# Aux_Lights_Daughter_REV2.net
KiCad netlist of a schematic drawn in Altium Designer
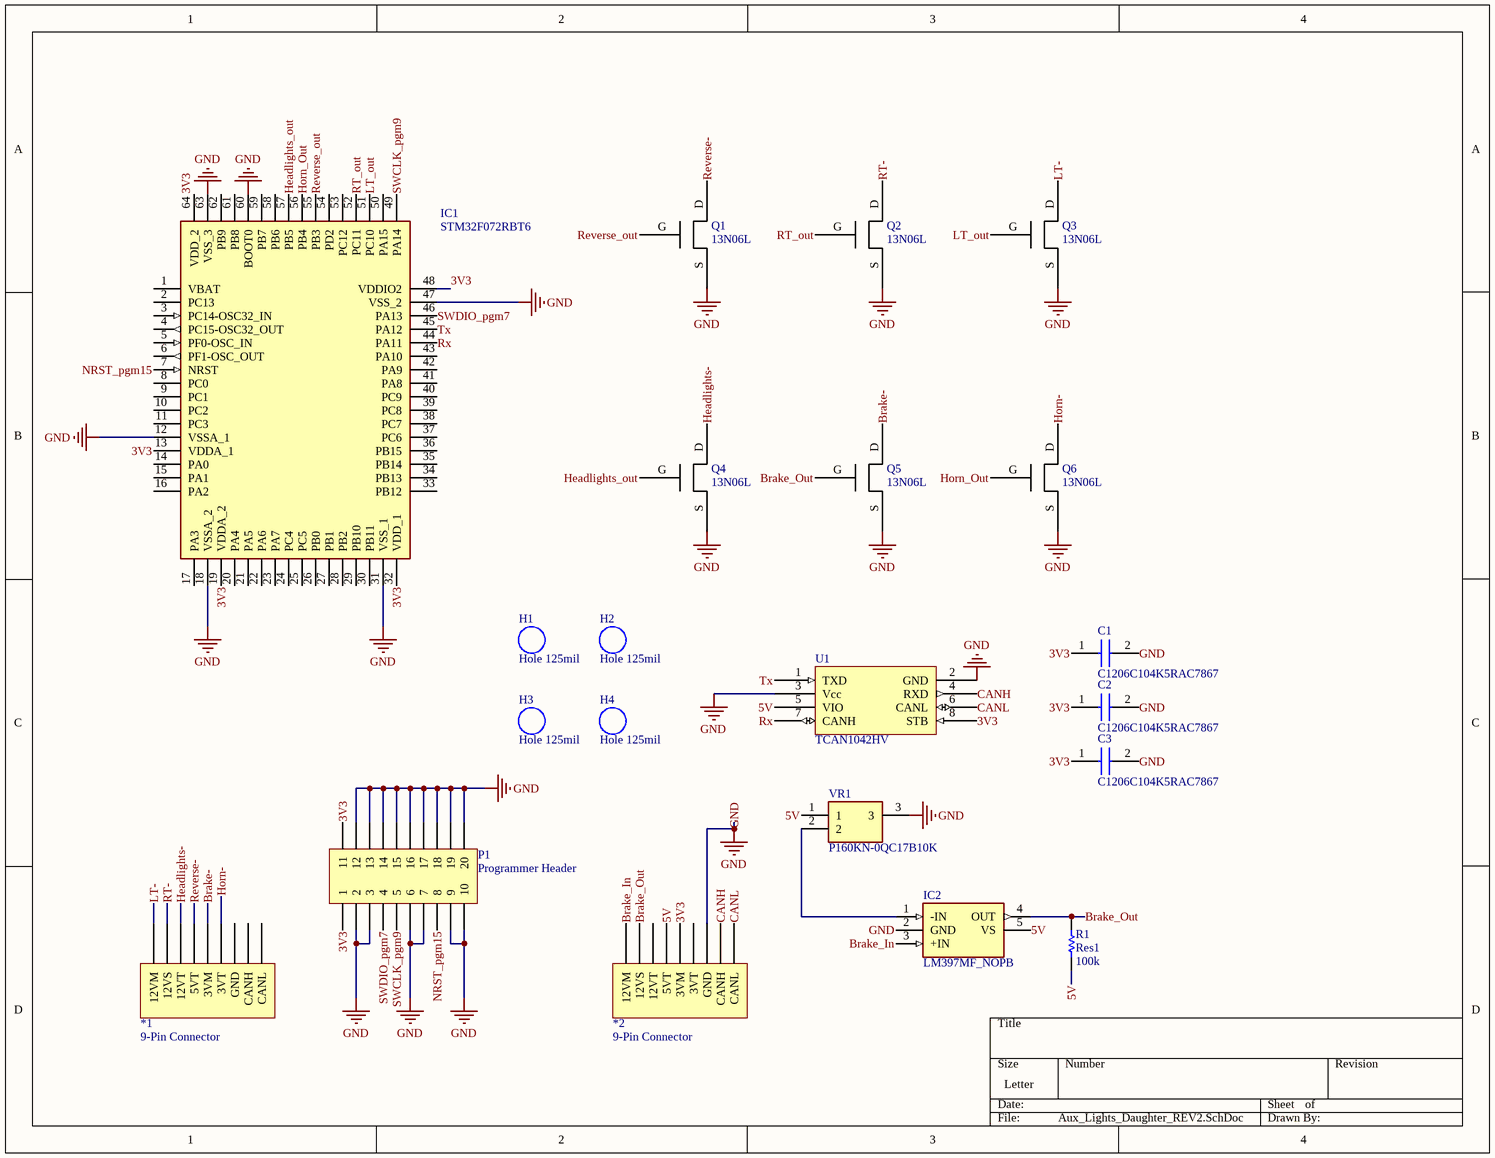
[diagram p0: Aux_Lights_Daughter_REV2.SchDoc]

(export (version "E")
  (design (tool "Eeschema 10.0.6"))
  (components
    (comp (ref "*1")
      (value "9-Pin Connector")
      (footprint "9-Pin")
      (libsource (lib "SolarGators") (part "9-Pin Connector"))
    )
    (comp (ref "*2")
      (value "9-Pin Connector")
      (footprint "9-Pin")
      (libsource (lib "SolarGators") (part "9-Pin Connector"))
    )
    (comp (ref "C1")
      (value "C1206C104K5RAC7867")
      (footprint "SamacSys:CAPC3216X110N")
      (description "Capacitor")
      (fields (field (name "MOUSER2 PART NUMBER") "80-C1206104K5RAC7867"))
      (libsource (lib "*") (part "C1206C104K5RAC7867"))
    )
    (comp (ref "C2")
      (value "C1206C104K5RAC7867")
      (footprint "SamacSys:CAPC3216X110N")
      (description "Capacitor")
      (fields (field (name "MOUSER2 PART NUMBER") "80-C1206104K5RAC7867"))
      (libsource (lib "*") (part "C1206C104K5RAC7867"))
    )
    (comp (ref "C3")
      (value "C1206C104K5RAC7867")
      (footprint "SamacSys:CAPC3216X110N")
      (description "Capacitor")
      (fields (field (name "MOUSER2 PART NUMBER") "80-C1206104K5RAC7867"))
      (libsource (lib "*") (part "C1206C104K5RAC7867"))
    )
    (comp (ref "H1")
      (value "Hole 125mil")
      (footprint "Hole 125mil")
      (libsource (lib "ECE LIB new") (part "Hole 125mil"))
    )
    (comp (ref "H2")
      (value "Hole 125mil")
      (footprint "Hole 125mil")
      (libsource (lib "ECE LIB new") (part "Hole 125mil"))
    )
    (comp (ref "H3")
      (value "Hole 125mil")
      (footprint "Hole 125mil")
      (libsource (lib "ECE LIB new") (part "Hole 125mil"))
    )
    (comp (ref "H4")
      (value "Hole 125mil")
      (footprint "Hole 125mil")
      (libsource (lib "ECE LIB new") (part "Hole 125mil"))
    )
    (comp (ref "IC1")
      (value "STM32F072RBT6")
      (footprint "QFP50P1200X1200X160-64N")
      (description "Integrated Circuit")
      (fields (field (name "MOUSER PART NUMBER") "511-STM32F072RBT6"))
      (libsource (lib "solargatorsproject") (part "STM32F072RBT6"))
    )
    (comp (ref "IC2")
      (value "LM397MF_NOPB")
      (footprint "SamacSys:SOT95P280X145-5N")
      (description "Integrated Circuit")
      (fields
        (field (name "MOUSER PART NUMBER") "926-LM397MF/NOPB")
        (field (name "MANUFACTURER_PART_NUMBER") "LM397MF/NOPB")
      )
      (libsource (lib "*") (part "LM397MF_NOPB"))
    )
    (comp (ref "P1")
      (value "Programmer Header")
      (footprint "HDR2X10_CEN")
      (description "Header, 10-Pin, Dual row")
      (fields (field (name "PUBLISHER") "Altium Limited"))
      (libsource (lib "Miscellaneous Connectors") (part "Header 10X2A"))
    )
    (comp (ref "Q1") (value "13N06L") (footprint "13N06L") (libsource (lib "SolarGators") (part "13N06L")))
    (comp (ref "Q2") (value "13N06L") (footprint "13N06L") (libsource (lib "SolarGators") (part "13N06L")))
    (comp (ref "Q3") (value "13N06L") (footprint "13N06L") (libsource (lib "SolarGators") (part "13N06L")))
    (comp (ref "Q4") (value "13N06L") (footprint "13N06L") (libsource (lib "SolarGators") (part "13N06L")))
    (comp (ref "Q5") (value "13N06L") (footprint "13N06L") (libsource (lib "SolarGators") (part "13N06L")))
    (comp (ref "Q6") (value "13N06L") (footprint "13N06L") (libsource (lib "SolarGators") (part "13N06L")))
    (comp (ref "R1")
      (value "Res1")
      (footprint "AXIAL-0.3")
      (description "Resistor")
      (fields (field (name "ALTIUM_VALUE") "100k") (field (name "PUBLISHER") "Altium Limited"))
      (libsource (lib "Miscellaneous Devices") (part "Res1"))
    )
    (comp (ref "U1")
      (value "TCAN1042HV")
      (footprint "CANIC")
      (description "TCAN1042Fault ProtectedCAN Transceiverwith CAN FD")
      (libsource (lib "Schlib1") (part "TCAN1042HV"))
    )
    (comp (ref "VR1")
      (value "P160KN-0QC17B10K")
      (footprint "POT inline wide")
      (description "Variable Resistor")
      (fields (field (name "MOUSER PART NUMBER") "858-P160KN-OQC17B10K"))
      (libsource (lib "*") (part "P160KN-0QC17B10K"))
    )
  )
  (nets
    (net (code "1") (name "/3V3") (class "Default")
      (node (ref "*2") (pin "5") (pinfunction "3VM_5") (pintype "passive"))
      (node (ref "C1") (pin "1") (pinfunction "1_1") (pintype "passive"))
      (node (ref "C2") (pin "1") (pinfunction "1_1") (pintype "passive"))
      (node (ref "C3") (pin "1") (pinfunction "1_1") (pintype "passive"))
      (node (ref "IC1") (pin "13") (pinfunction "VDDA_1_13") (pintype "power_in"))
      (node (ref "IC1") (pin "19") (pinfunction "VDDA_2_19") (pintype "power_in"))
      (node (ref "IC1") (pin "32") (pinfunction "VDD_1_32") (pintype "power_in"))
      (node (ref "IC1") (pin "48") (pinfunction "VDDIO2_48") (pintype "power_in"))
      (node (ref "IC1") (pin "64") (pinfunction "VDD_2_64") (pintype "power_in"))
      (node (ref "P1") (pin "1") (pinfunction "1_1") (pintype "passive"))
      (node (ref "P1") (pin "11") (pinfunction "11_11") (pintype "passive"))
      (node (ref "U1") (pin "8") (pinfunction "STB_8") (pintype "input"))
    )
    (net (code "2") (name "/5V") (class "Default")
      (node (ref "*2") (pin "4") (pinfunction "5VT_4") (pintype "passive"))
      (node (ref "IC2") (pin "5") (pinfunction "VS_5") (pintype "passive"))
      (node (ref "R1") (pin "1") (pinfunction "1_1") (pintype "passive"))
      (node (ref "U1") (pin "5") (pinfunction "VIO_5") (pintype "power_in"))
      (node (ref "VR1") (pin "1") (pinfunction "1_1") (pintype "passive"))
    )
    (net (code "3") (name "/Brake-") (class "Default")
      (node (ref "*1") (pin "5") (pinfunction "3VM_5") (pintype "passive"))
      (node (ref "Q5") (pin "D") (pinfunction "14_D") (pintype "passive"))
    )
    (net (code "4") (name "/Brake_In") (class "Default")
      (node (ref "*2") (pin "1") (pinfunction "12VM_1") (pintype "passive"))
      (node (ref "IC2") (pin "3") (pinfunction "+IN_3") (pintype "input"))
    )
    (net (code "5") (name "/Brake_Out") (class "Default")
      (node (ref "*2") (pin "2") (pinfunction "12VS_2") (pintype "passive"))
      (node (ref "IC2") (pin "4") (pinfunction "OUT_4") (pintype "output"))
      (node (ref "Q5") (pin "G") (pinfunction "13_G") (pintype "passive"))
      (node (ref "R1") (pin "2") (pinfunction "2_2") (pintype "passive"))
    )
    (net (code "6") (name "/CANH") (class "Default")
      (node (ref "*2") (pin "8") (pinfunction "CANH_8") (pintype "passive"))
      (node (ref "U1") (pin "4") (pinfunction "RXD_4") (pintype "output"))
    )
    (net (code "7") (name "/CANL") (class "Default")
      (node (ref "*2") (pin "9") (pinfunction "CANL_9") (pintype "passive"))
      (node (ref "U1") (pin "6") (pinfunction "CANL_6") (pintype "bidirectional"))
    )
    (net (code "8") (name "/Headlights-") (class "Default")
      (node (ref "*1") (pin "3") (pinfunction "12VT_3") (pintype "passive"))
      (node (ref "Q4") (pin "D") (pinfunction "14_D") (pintype "passive"))
    )
    (net (code "9") (name "/Headlights_out") (class "Default")
      (node (ref "IC1") (pin "57") (pinfunction "PB5_57") (pintype "passive"))
      (node (ref "Q4") (pin "G") (pinfunction "13_G") (pintype "passive"))
    )
    (net (code "10") (name "/Horn-") (class "Default")
      (node (ref "*1") (pin "6") (pinfunction "3VT_6") (pintype "passive"))
      (node (ref "Q6") (pin "D") (pinfunction "14_D") (pintype "passive"))
    )
    (net (code "11") (name "/Horn_Out") (class "Default")
      (node (ref "IC1") (pin "56") (pinfunction "PB4_56") (pintype "passive"))
      (node (ref "Q6") (pin "G") (pinfunction "13_G") (pintype "passive"))
    )
    (net (code "12") (name "/LT-") (class "Default")
      (node (ref "*1") (pin "1") (pinfunction "12VM_1") (pintype "passive"))
      (node (ref "Q3") (pin "D") (pinfunction "14_D") (pintype "passive"))
    )
    (net (code "13") (name "/LT_out") (class "Default")
      (node (ref "IC1") (pin "51") (pinfunction "PC10_51") (pintype "passive"))
      (node (ref "Q3") (pin "G") (pinfunction "13_G") (pintype "passive"))
    )
    (net (code "14") (name "/NRST_pgm15") (class "Default")
      (node (ref "IC1") (pin "7") (pinfunction "NRST_7") (pintype "input"))
      (node (ref "P1") (pin "8") (pinfunction "8_8") (pintype "passive"))
    )
    (net (code "15") (name "/RT-") (class "Default")
      (node (ref "*1") (pin "2") (pinfunction "12VS_2") (pintype "passive"))
      (node (ref "Q2") (pin "D") (pinfunction "14_D") (pintype "passive"))
    )
    (net (code "16") (name "/RT_out") (class "Default")
      (node (ref "IC1") (pin "52") (pinfunction "PC11_52") (pintype "passive"))
      (node (ref "Q2") (pin "G") (pinfunction "13_G") (pintype "passive"))
    )
    (net (code "17") (name "/Reverse-") (class "Default")
      (node (ref "*1") (pin "4") (pinfunction "5VT_4") (pintype "passive"))
      (node (ref "Q1") (pin "D") (pinfunction "14_D") (pintype "passive"))
    )
    (net (code "18") (name "/Reverse_out") (class "Default")
      (node (ref "IC1") (pin "55") (pinfunction "PB3_55") (pintype "passive"))
      (node (ref "Q1") (pin "G") (pinfunction "13_G") (pintype "passive"))
    )
    (net (code "19") (name "/Rx") (class "Default")
      (node (ref "IC1") (pin "44") (pinfunction "PA11_44") (pintype "passive"))
      (node (ref "U1") (pin "7") (pinfunction "CANH_7") (pintype "bidirectional"))
    )
    (net (code "20") (name "/SWCLK_pgm9") (class "Default")
      (node (ref "IC1") (pin "49") (pinfunction "PA14_49") (pintype "passive"))
      (node (ref "P1") (pin "5") (pinfunction "5_5") (pintype "passive"))
    )
    (net (code "21") (name "/SWDIO_pgm7") (class "Default")
      (node (ref "IC1") (pin "46") (pinfunction "PA13_46") (pintype "passive"))
      (node (ref "P1") (pin "4") (pinfunction "4_4") (pintype "passive"))
    )
    (net (code "22") (name "/Tx") (class "Default")
      (node (ref "IC1") (pin "45") (pinfunction "PA12_45") (pintype "passive"))
      (node (ref "U1") (pin "1") (pinfunction "TXD_1") (pintype "input"))
    )
    (net (code "23") (name "GND") (class "Default")
      (node (ref "*2") (pin "7") (pinfunction "GND_7") (pintype "passive"))
      (node (ref "C1") (pin "2") (pinfunction "2_2") (pintype "passive"))
      (node (ref "C2") (pin "2") (pinfunction "2_2") (pintype "passive"))
      (node (ref "C3") (pin "2") (pinfunction "2_2") (pintype "passive"))
      (node (ref "IC1") (pin "12") (pinfunction "VSSA_1_12") (pintype "power_in"))
      (node (ref "IC1") (pin "18") (pinfunction "VSSA_2_18") (pintype "power_in"))
      (node (ref "IC1") (pin "31") (pinfunction "VSS_1_31") (pintype "power_in"))
      (node (ref "IC1") (pin "47") (pinfunction "VSS_2_47") (pintype "power_in"))
      (node (ref "IC1") (pin "60") (pinfunction "BOOT0_60") (pintype "passive"))
      (node (ref "IC1") (pin "63") (pinfunction "VSS_3_63") (pintype "power_in"))
      (node (ref "IC2") (pin "2") (pinfunction "GND_2") (pintype "power_in"))
      (node (ref "P1") (pin "10") (pinfunction "10_10") (pintype "passive"))
      (node (ref "P1") (pin "12") (pinfunction "12_12") (pintype "passive"))
      (node (ref "P1") (pin "13") (pinfunction "13_13") (pintype "passive"))
      (node (ref "P1") (pin "14") (pinfunction "14_14") (pintype "passive"))
      (node (ref "P1") (pin "15") (pinfunction "15_15") (pintype "passive"))
      (node (ref "P1") (pin "16") (pinfunction "16_16") (pintype "passive"))
      (node (ref "P1") (pin "17") (pinfunction "17_17") (pintype "passive"))
      (node (ref "P1") (pin "18") (pinfunction "18_18") (pintype "passive"))
      (node (ref "P1") (pin "19") (pinfunction "19_19") (pintype "passive"))
      (node (ref "P1") (pin "2") (pinfunction "2_2") (pintype "passive"))
      (node (ref "P1") (pin "20") (pinfunction "20_20") (pintype "passive"))
      (node (ref "P1") (pin "3") (pinfunction "3_3") (pintype "passive"))
      (node (ref "P1") (pin "6") (pinfunction "6_6") (pintype "passive"))
      (node (ref "P1") (pin "7") (pinfunction "7_7") (pintype "passive"))
      (node (ref "P1") (pin "9") (pinfunction "9_9") (pintype "passive"))
      (node (ref "Q1") (pin "S") (pinfunction "15_S") (pintype "passive"))
      (node (ref "Q2") (pin "S") (pinfunction "15_S") (pintype "passive"))
      (node (ref "Q3") (pin "S") (pinfunction "15_S") (pintype "passive"))
      (node (ref "Q4") (pin "S") (pinfunction "15_S") (pintype "passive"))
      (node (ref "Q5") (pin "S") (pinfunction "15_S") (pintype "passive"))
      (node (ref "Q6") (pin "S") (pinfunction "15_S") (pintype "passive"))
      (node (ref "U1") (pin "2") (pinfunction "GND_2") (pintype "power_in"))
      (node (ref "U1") (pin "3") (pinfunction "Vcc_3") (pintype "power_in"))
      (node (ref "VR1") (pin "3") (pinfunction "3_3") (pintype "passive"))
    )
    (net (code "24") (name "Net-(IC2--IN)") (class "Default")
      (node (ref "IC2") (pin "1") (pinfunction "-IN_1") (pintype "input"))
      (node (ref "VR1") (pin "2") (pinfunction "2_2") (pintype "passive"))
    )
    (net (code "25") (name "unconnected-(*1-CANH-Pad8)") (class "Default")
      (node (ref "*1") (pin "8") (pinfunction "CANH_8") (pintype "passive"))
    )
    (net (code "26") (name "unconnected-(*1-CANL-Pad9)") (class "Default")
      (node (ref "*1") (pin "9") (pinfunction "CANL_9") (pintype "passive"))
    )
    (net (code "27") (name "unconnected-(*1-GND-Pad7)") (class "Default")
      (node (ref "*1") (pin "7") (pinfunction "GND_7") (pintype "passive"))
    )
    (net (code "28") (name "unconnected-(*2-3VT-Pad6)") (class "Default")
      (node (ref "*2") (pin "6") (pinfunction "3VT_6") (pintype "passive"))
    )
    (net (code "29") (name "unconnected-(*2-12VT-Pad3)") (class "Default")
      (node (ref "*2") (pin "3") (pinfunction "12VT_3") (pintype "passive"))
    )
    (net (code "30") (name "unconnected-(IC1-PA0-Pad14)") (class "Default")
      (node (ref "IC1") (pin "14") (pinfunction "PA0_14") (pintype "passive"))
    )
    (net (code "31") (name "unconnected-(IC1-PA1-Pad15)") (class "Default")
      (node (ref "IC1") (pin "15") (pinfunction "PA1_15") (pintype "passive"))
    )
    (net (code "32") (name "unconnected-(IC1-PA2-Pad16)") (class "Default")
      (node (ref "IC1") (pin "16") (pinfunction "PA2_16") (pintype "passive"))
    )
    (net (code "33") (name "unconnected-(IC1-PA3-Pad17)") (class "Default")
      (node (ref "IC1") (pin "17") (pinfunction "PA3_17") (pintype "passive"))
    )
    (net (code "34") (name "unconnected-(IC1-PA4-Pad20)") (class "Default")
      (node (ref "IC1") (pin "20") (pinfunction "PA4_20") (pintype "passive"))
    )
    (net (code "35") (name "unconnected-(IC1-PA5-Pad21)") (class "Default")
      (node (ref "IC1") (pin "21") (pinfunction "PA5_21") (pintype "passive"))
    )
    (net (code "36") (name "unconnected-(IC1-PA6-Pad22)") (class "Default")
      (node (ref "IC1") (pin "22") (pinfunction "PA6_22") (pintype "passive"))
    )
    (net (code "37") (name "unconnected-(IC1-PA7-Pad23)") (class "Default")
      (node (ref "IC1") (pin "23") (pinfunction "PA7_23") (pintype "passive"))
    )
    (net (code "38") (name "unconnected-(IC1-PA8-Pad41)") (class "Default")
      (node (ref "IC1") (pin "41") (pinfunction "PA8_41") (pintype "passive"))
    )
    (net (code "39") (name "unconnected-(IC1-PA9-Pad42)") (class "Default")
      (node (ref "IC1") (pin "42") (pinfunction "PA9_42") (pintype "passive"))
    )
    (net (code "40") (name "unconnected-(IC1-PA10-Pad43)") (class "Default")
      (node (ref "IC1") (pin "43") (pinfunction "PA10_43") (pintype "passive"))
    )
    (net (code "41") (name "unconnected-(IC1-PA15-Pad50)") (class "Default")
      (node (ref "IC1") (pin "50") (pinfunction "PA15_50") (pintype "passive"))
    )
    (net (code "42") (name "unconnected-(IC1-PB0-Pad26)") (class "Default")
      (node (ref "IC1") (pin "26") (pinfunction "PB0_26") (pintype "passive"))
    )
    (net (code "43") (name "unconnected-(IC1-PB1-Pad27)") (class "Default")
      (node (ref "IC1") (pin "27") (pinfunction "PB1_27") (pintype "passive"))
    )
    (net (code "44") (name "unconnected-(IC1-PB2-Pad28)") (class "Default")
      (node (ref "IC1") (pin "28") (pinfunction "PB2_28") (pintype "passive"))
    )
    (net (code "45") (name "unconnected-(IC1-PB6-Pad58)") (class "Default")
      (node (ref "IC1") (pin "58") (pinfunction "PB6_58") (pintype "passive"))
    )
    (net (code "46") (name "unconnected-(IC1-PB7-Pad59)") (class "Default")
      (node (ref "IC1") (pin "59") (pinfunction "PB7_59") (pintype "passive"))
    )
    (net (code "47") (name "unconnected-(IC1-PB8-Pad61)") (class "Default")
      (node (ref "IC1") (pin "61") (pinfunction "PB8_61") (pintype "passive"))
    )
    (net (code "48") (name "unconnected-(IC1-PB9-Pad62)") (class "Default")
      (node (ref "IC1") (pin "62") (pinfunction "PB9_62") (pintype "passive"))
    )
    (net (code "49") (name "unconnected-(IC1-PB10-Pad29)") (class "Default")
      (node (ref "IC1") (pin "29") (pinfunction "PB10_29") (pintype "passive"))
    )
    (net (code "50") (name "unconnected-(IC1-PB11-Pad30)") (class "Default")
      (node (ref "IC1") (pin "30") (pinfunction "PB11_30") (pintype "passive"))
    )
    (net (code "51") (name "unconnected-(IC1-PB12-Pad33)") (class "Default")
      (node (ref "IC1") (pin "33") (pinfunction "PB12_33") (pintype "passive"))
    )
    (net (code "52") (name "unconnected-(IC1-PB13-Pad34)") (class "Default")
      (node (ref "IC1") (pin "34") (pinfunction "PB13_34") (pintype "passive"))
    )
    (net (code "53") (name "unconnected-(IC1-PB14-Pad35)") (class "Default")
      (node (ref "IC1") (pin "35") (pinfunction "PB14_35") (pintype "passive"))
    )
    (net (code "54") (name "unconnected-(IC1-PB15-Pad36)") (class "Default")
      (node (ref "IC1") (pin "36") (pinfunction "PB15_36") (pintype "passive"))
    )
    (net (code "55") (name "unconnected-(IC1-PC0-Pad8)") (class "Default")
      (node (ref "IC1") (pin "8") (pinfunction "PC0_8") (pintype "passive"))
    )
    (net (code "56") (name "unconnected-(IC1-PC1-Pad9)") (class "Default")
      (node (ref "IC1") (pin "9") (pinfunction "PC1_9") (pintype "passive"))
    )
    (net (code "57") (name "unconnected-(IC1-PC2-Pad10)") (class "Default")
      (node (ref "IC1") (pin "10") (pinfunction "PC2_10") (pintype "passive"))
    )
    (net (code "58") (name "unconnected-(IC1-PC3-Pad11)") (class "Default")
      (node (ref "IC1") (pin "11") (pinfunction "PC3_11") (pintype "passive"))
    )
    (net (code "59") (name "unconnected-(IC1-PC4-Pad24)") (class "Default")
      (node (ref "IC1") (pin "24") (pinfunction "PC4_24") (pintype "passive"))
    )
    (net (code "60") (name "unconnected-(IC1-PC5-Pad25)") (class "Default")
      (node (ref "IC1") (pin "25") (pinfunction "PC5_25") (pintype "passive"))
    )
    (net (code "61") (name "unconnected-(IC1-PC6-Pad37)") (class "Default")
      (node (ref "IC1") (pin "37") (pinfunction "PC6_37") (pintype "passive"))
    )
    (net (code "62") (name "unconnected-(IC1-PC7-Pad38)") (class "Default")
      (node (ref "IC1") (pin "38") (pinfunction "PC7_38") (pintype "passive"))
    )
    (net (code "63") (name "unconnected-(IC1-PC8-Pad39)") (class "Default")
      (node (ref "IC1") (pin "39") (pinfunction "PC8_39") (pintype "passive"))
    )
    (net (code "64") (name "unconnected-(IC1-PC9-Pad40)") (class "Default")
      (node (ref "IC1") (pin "40") (pinfunction "PC9_40") (pintype "passive"))
    )
    (net (code "65") (name "unconnected-(IC1-PC12-Pad53)") (class "Default")
      (node (ref "IC1") (pin "53") (pinfunction "PC12_53") (pintype "passive"))
    )
    (net (code "66") (name "unconnected-(IC1-PC13-Pad2)") (class "Default")
      (node (ref "IC1") (pin "2") (pinfunction "PC13_2") (pintype "passive"))
    )
    (net (code "67") (name "unconnected-(IC1-PC14-OSC32_IN-Pad3)") (class "Default")
      (node (ref "IC1") (pin "3") (pinfunction "PC14-OSC32_IN_3") (pintype "input"))
    )
    (net (code "68") (name "unconnected-(IC1-PC15-OSC32_OUT-Pad4)") (class "Default")
      (node (ref "IC1") (pin "4") (pinfunction "PC15-OSC32_OUT_4") (pintype "output"))
    )
    (net (code "69") (name "unconnected-(IC1-PD2-Pad54)") (class "Default")
      (node (ref "IC1") (pin "54") (pinfunction "PD2_54") (pintype "passive"))
    )
    (net (code "70") (name "unconnected-(IC1-PF0-OSC_IN-Pad5)") (class "Default")
      (node (ref "IC1") (pin "5") (pinfunction "PF0-OSC_IN_5") (pintype "input"))
    )
    (net (code "71") (name "unconnected-(IC1-PF1-OSC_OUT-Pad6)") (class "Default")
      (node (ref "IC1") (pin "6") (pinfunction "PF1-OSC_OUT_6") (pintype "output"))
    )
    (net (code "72") (name "unconnected-(IC1-VBAT-Pad1)") (class "Default")
      (node (ref "IC1") (pin "1") (pinfunction "VBAT_1") (pintype "passive"))
    )
  )
)
